# Controller.net
KiCad netlist of a schematic drawn in Altium Designer
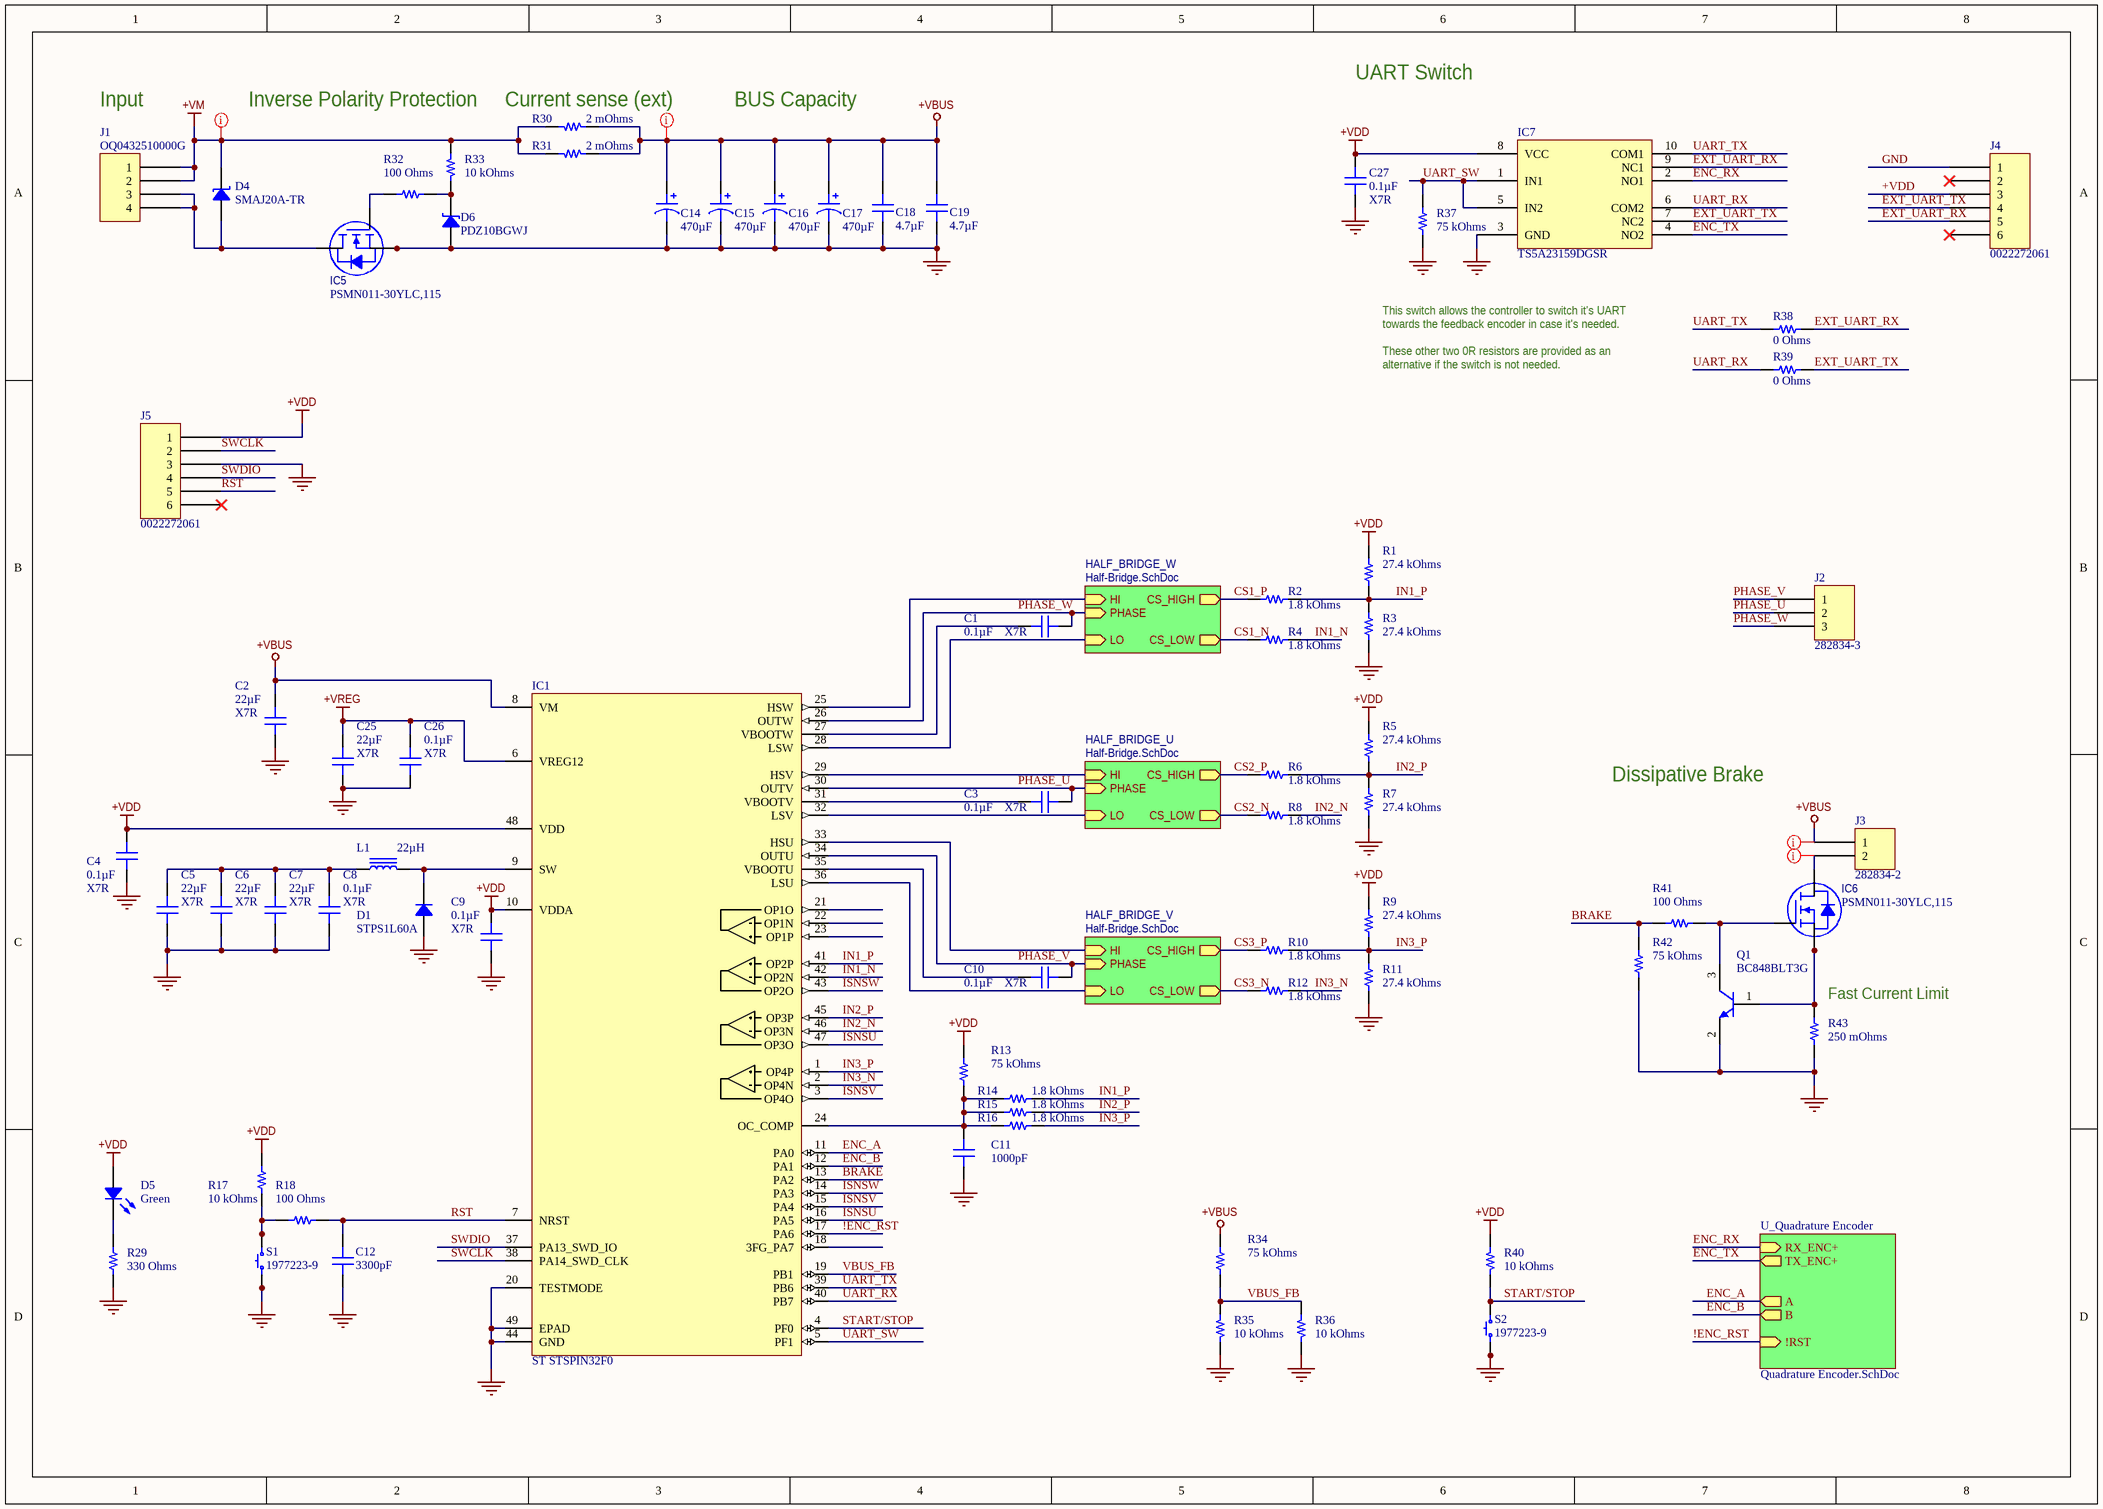
[diagram p0: Controller.SchDoc]

(export (version "E")
  (design (tool "Eeschema 10.0.6"))
  (components
    (comp (ref "C1")
      (value "0.1µF")
      (footprint "CAP 0805_2012")
      (description "CAP CER 0.1UF 50V X7R 0805")
      (fields
        (field (name "PART NUMBER") "CL21B104KBCWPNC")
        (field (name "MANUFACTURER") "Samsung Electro-Mechanics")
        (field (name "TEMPERATURE COEFFICIENT") "X7R")
      )
      (libsource (lib "Celestial Altium Library - altium_library") (part "Capacitor"))
    )
    (comp (ref "C2")
      (value "22µF")
      (footprint "CAP 1206_3216 - 1.8MM")
      (description "CAP CER 22UF 6.3V X7R 1206")
      (fields
        (field (name "PART NUMBER") "GCM31CR70J226KE23L")
        (field (name "MANUFACTURER") "Murata Electronics")
        (field (name "TEMPERATURE COEFFICIENT") "X7R")
      )
      (libsource (lib "Celestial Altium Library - altium_library") (part "Capacitor"))
    )
    (comp (ref "C3")
      (value "0.1µF")
      (footprint "CAP 0805_2012")
      (description "CAP CER 0.1UF 50V X7R 0805")
      (fields
        (field (name "PART NUMBER") "CL21B104KBCWPNC")
        (field (name "MANUFACTURER") "Samsung Electro-Mechanics")
        (field (name "TEMPERATURE COEFFICIENT") "X7R")
      )
      (libsource (lib "Celestial Altium Library - altium_library") (part "Capacitor"))
    )
    (comp (ref "C4")
      (value "0.1µF")
      (footprint "CAP 0805_2012")
      (description "CAP CER 0.1UF 50V X7R 0805")
      (fields
        (field (name "PART NUMBER") "CL21B104KBCWPNC")
        (field (name "MANUFACTURER") "Samsung Electro-Mechanics")
        (field (name "TEMPERATURE COEFFICIENT") "X7R")
      )
      (libsource (lib "Celestial Altium Library - altium_library") (part "Capacitor"))
    )
    (comp (ref "C5")
      (value "22µF")
      (footprint "CAP 1206_3216 - 1.8MM")
      (description "CAP CER 22UF 6.3V X7R 1206")
      (fields
        (field (name "PART NUMBER") "GCM31CR70J226KE23L")
        (field (name "MANUFACTURER") "Murata Electronics")
        (field (name "TEMPERATURE COEFFICIENT") "X7R")
      )
      (libsource (lib "Celestial Altium Library - altium_library") (part "Capacitor"))
    )
    (comp (ref "C6")
      (value "22µF")
      (footprint "CAP 1206_3216 - 1.8MM")
      (description "CAP CER 22UF 6.3V X7R 1206")
      (fields
        (field (name "PART NUMBER") "GCM31CR70J226KE23L")
        (field (name "MANUFACTURER") "Murata Electronics")
        (field (name "TEMPERATURE COEFFICIENT") "X7R")
      )
      (libsource (lib "Celestial Altium Library - altium_library") (part "Capacitor"))
    )
    (comp (ref "C7")
      (value "22µF")
      (footprint "CAP 1206_3216 - 1.8MM")
      (description "CAP CER 22UF 6.3V X7R 1206")
      (fields
        (field (name "PART NUMBER") "GCM31CR70J226KE23L")
        (field (name "MANUFACTURER") "Murata Electronics")
        (field (name "TEMPERATURE COEFFICIENT") "X7R")
      )
      (libsource (lib "Celestial Altium Library - altium_library") (part "Capacitor"))
    )
    (comp (ref "C8")
      (value "0.1µF")
      (footprint "CAP 0805_2012")
      (description "CAP CER 0.1UF 50V X7R 0805")
      (fields
        (field (name "PART NUMBER") "CL21B104KBCWPNC")
        (field (name "MANUFACTURER") "Samsung Electro-Mechanics")
        (field (name "TEMPERATURE COEFFICIENT") "X7R")
      )
      (libsource (lib "Celestial Altium Library - altium_library") (part "Capacitor"))
    )
    (comp (ref "C9")
      (value "0.1µF")
      (footprint "CAP 0805_2012")
      (description "CAP CER 0.1UF 50V X7R 0805")
      (fields
        (field (name "PART NUMBER") "CL21B104KBCWPNC")
        (field (name "MANUFACTURER") "Samsung Electro-Mechanics")
        (field (name "TEMPERATURE COEFFICIENT") "X7R")
      )
      (libsource (lib "Celestial Altium Library - altium_library") (part "Capacitor"))
    )
    (comp (ref "C10")
      (value "0.1µF")
      (footprint "CAP 0805_2012")
      (description "CAP CER 0.1UF 50V X7R 0805")
      (fields
        (field (name "PART NUMBER") "CL21B104KBCWPNC")
        (field (name "MANUFACTURER") "Samsung Electro-Mechanics")
        (field (name "TEMPERATURE COEFFICIENT") "X7R")
      )
      (libsource (lib "Celestial Altium Library - altium_library") (part "Capacitor"))
    )
    (comp (ref "C11")
      (value "1000pF")
      (footprint "CAP 0603_1608")
      (description "CAP CER 0603 1NF 16V X7R 10%")
      (fields (field (name "PART NUMBER") "C0603C102K4RECAUTO") (field (name "MANUFACTURER") "KEMET"))
      (libsource (lib "Celestial Altium Library - altium_library") (part "Capacitor"))
    )
    (comp (ref "C12")
      (value "3300pF")
      (footprint "CAP 0603_1608")
      (description "CAP CER 3300PF 25V NP0 0603")
      (fields (field (name "PART NUMBER") "C0603C332J3GAC7867") (field (name "MANUFACTURER") "KEMET"))
      (libsource (lib "Celestial Altium Library - altium_library") (part "Capacitor"))
    )
    (comp (ref "C14")
      (value "470µF")
      (footprint "CAP ALSMD 8.3MM H10.5MM")
      (description "CAP ALUM 470UF 20% 25V SMD")
      (fields (field (name "PART NUMBER") "25TPV470M8X10.5") (field (name "MANUFACTURER") "Rubycon"))
      (libsource (lib "Celestial Altium Library - altium_library") (part "Polarised Capacitor"))
    )
    (comp (ref "C15")
      (value "470µF")
      (footprint "CAP ALSMD 8.3MM H10.5MM")
      (description "CAP ALUM 470UF 20% 25V SMD")
      (fields (field (name "PART NUMBER") "25TPV470M8X10.5") (field (name "MANUFACTURER") "Rubycon"))
      (libsource (lib "Celestial Altium Library - altium_library") (part "Polarised Capacitor"))
    )
    (comp (ref "C16")
      (value "470µF")
      (footprint "CAP ALSMD 8.3MM H10.5MM")
      (description "CAP ALUM 470UF 20% 25V SMD")
      (fields (field (name "PART NUMBER") "25TPV470M8X10.5") (field (name "MANUFACTURER") "Rubycon"))
      (libsource (lib "Celestial Altium Library - altium_library") (part "Polarised Capacitor"))
    )
    (comp (ref "C17")
      (value "470µF")
      (footprint "CAP ALSMD 8.3MM H10.5MM")
      (description "CAP ALUM 470UF 20% 25V SMD")
      (fields (field (name "PART NUMBER") "25TPV470M8X10.5") (field (name "MANUFACTURER") "Rubycon"))
      (libsource (lib "Celestial Altium Library - altium_library") (part "Polarised Capacitor"))
    )
    (comp (ref "C18")
      (value "4.7µF")
      (footprint "CAP 1206_3216 - 1.8MM")
      (description "CAP CER 4.7UF 25V X7R 1206")
      (fields
        (field (name "PART NUMBER") "GCM31CR71E475KA55L")
        (field (name "MANUFACTURER") "Murata Electronics")
      )
      (libsource (lib "Celestial Altium Library - altium_library") (part "Capacitor"))
    )
    (comp (ref "C19")
      (value "4.7µF")
      (footprint "CAP 1206_3216 - 1.8MM")
      (description "CAP CER 4.7UF 25V X7R 1206")
      (fields
        (field (name "PART NUMBER") "GCM31CR71E475KA55L")
        (field (name "MANUFACTURER") "Murata Electronics")
      )
      (libsource (lib "Celestial Altium Library - altium_library") (part "Capacitor"))
    )
    (comp (ref "C25")
      (value "22µF")
      (footprint "CAP 1206_3216 - 1.8MM")
      (description "CAP CER 22UF 6.3V X7R 1206")
      (fields
        (field (name "PART NUMBER") "GCM31CR70J226KE23L")
        (field (name "MANUFACTURER") "Murata Electronics")
        (field (name "TEMPERATURE COEFFICIENT") "X7R")
      )
      (libsource (lib "Celestial Altium Library - altium_library") (part "Capacitor"))
    )
    (comp (ref "C26")
      (value "0.1µF")
      (footprint "CAP 0805_2012")
      (description "CAP CER 0.1UF 50V X7R 0805")
      (fields
        (field (name "PART NUMBER") "CL21B104KBCWPNC")
        (field (name "MANUFACTURER") "Samsung Electro-Mechanics")
        (field (name "TEMPERATURE COEFFICIENT") "X7R")
      )
      (libsource (lib "Celestial Altium Library - altium_library") (part "Capacitor"))
    )
    (comp (ref "C27")
      (value "0.1µF")
      (footprint "CAP 0805_2012")
      (description "CAP CER 0.1UF 50V X7R 0805")
      (fields
        (field (name "PART NUMBER") "CL21B104KBCWPNC")
        (field (name "MANUFACTURER") "Samsung Electro-Mechanics")
        (field (name "TEMPERATURE COEFFICIENT") "X7R")
      )
      (libsource (lib "Celestial Altium Library - altium_library") (part "Capacitor"))
    )
    (comp (ref "D1")
      (value "STPS1L60A")
      (footprint "DO214AC SMA")
      (description "DIODE SCHOTTKY 60V 1A SMA")
      (fields (field (name "MANUFACTURER") "STMicroelectronics"))
      (libsource (lib "Celestial Altium Library - altium_library") (part "Diode"))
    )
    (comp (ref "D4")
      (value "SMAJ20A-TR")
      (footprint "DO214AC SMA")
      (description "TVS DIODE 20V 42.8V SMA")
      (fields (field (name "MANUFACTURER") "STMicroelectronics"))
      (libsource (lib "Celestial Altium Library - altium_library") (part "DIODE TVS UNI"))
    )
    (comp (ref "D5")
      (value "Green")
      (footprint "LED 0603_1608 GREEN")
      (description "LED GREEN DIFFUSED 0603 SMD")
      (fields (field (name "PART NUMBER") "SML-D12P8WT86") (field (name "MANUFACTURER") "Rohm Semiconductor"))
      (libsource (lib "Celestial Altium Library - altium_library") (part "LED"))
    )
    (comp (ref "D6")
      (value "PDZ10BGWJ")
      (footprint "SOD-123")
      (description "DIODE ZENER 10V 365MW SOD123")
      (fields (field (name "MANUFACTURER") "Nexperia USA Inc.") (field (name "TOLERANCE") "±2.2%"))
      (libsource (lib "Celestial Altium Library - altium_library") (part "Diode Zener"))
    )
    (comp (ref "IC1")
      (value "ST STSPIN32F0")
      (footprint "PCB - LEADLESS - QFN - ST VFQFPN48 EP 5x5MM:ST VFQFPN48EP 7x7MM")
      (libsource (lib "SCH - MICROCONTROLLER - ST STSPIN32F0") (part "ST STSPIN32F0"))
    )
    (comp (ref "IC5")
      (value "PSMN011-30YLC,115")
      (footprint "NXP LFPAK56 SOT669")
      (description "MOSFET N-CH 30V 37A LFPAK")
      (fields (field (name "MANUFACTURER") "Nexperia USA Inc."))
      (libsource (lib "") (part "NEXPERIA PSMN LFPAK MOSFET N-CH_1"))
    )
    (comp (ref "IC6")
      (value "PSMN011-30YLC,115")
      (footprint "NXP LFPAK56 SOT669")
      (description "MOSFET N-CH 30V 37A LFPAK")
      (fields (field (name "MANUFACTURER") "Nexperia USA Inc."))
      (libsource (lib "Celestial Altium Library - altium_library") (part "NEXPERIA PSMN LFPAK MOSFET N-CH"))
    )
    (comp (ref "IC7")
      (value "TS5A23159DGSR")
      (footprint "TI MSOP-10 DGS")
      (description "IC SWITCH SPDT DUAL 10VSSOP")
      (fields (field (name "MANUFACTURER") "Texas Instruments"))
      (libsource (lib "Celestial Altium Library - altium_library") (part "TI TS5A23159"))
    )
    (comp (ref "J1")
      (value "OQ0432510000G")
      (footprint "FCI 06-381-4PIN")
      (description "TERM BLOCK HDR 4POS 90DEG 3.81MM")
      (fields (field (name "MANUFACTURER") "Amphenol Anytek"))
      (libsource (lib "Celestial Altium Library - altium_library") (part "4 Pin"))
    )
    (comp (ref "J2")
      (value "282834-3")
      (footprint "TE 282834-3")
      (description "TERM BLK 3P SIDE ENT 2.54MM PCB")
      (fields (field (name "MANUFACTURER") "TE Connectivity AMP Connectors") (field (name "VOLTAGE") "150V"))
      (libsource (lib "Celestial Altium Library - altium_library") (part "3 Pin"))
    )
    (comp (ref "J3")
      (value "282834-2")
      (footprint "TE 282834-2")
      (description "TERM BLK 2P SIDE ENT 2.54MM PCB")
      (fields (field (name "MANUFACTURER") "TE Connectivity AMP Connectors") (field (name "VOLTAGE") "150V"))
      (libsource (lib "Celestial Altium Library - altium_library") (part "2 Pin"))
    )
    (comp (ref "J4")
      (value "0022272061")
      (footprint "MOLEX KK 0022272061")
      (description "CONN HEADER VERT 6POS 2.54MM")
      (fields (field (name "MANUFACTURER") "Molex"))
      (libsource (lib "") (part "6 Pin_1"))
    )
    (comp (ref "J5")
      (value "0022272061")
      (footprint "MOLEX KK 0022272061")
      (description "CONN HEADER VERT 6POS 2.54MM")
      (fields (field (name "MANUFACTURER") "Molex"))
      (libsource (lib "Celestial Altium Library - altium_library") (part "6 Pin"))
    )
    (comp (ref "L1")
      (value "22µH")
      (footprint "BOURNS SRN3015")
      (description "FIXED IND 22UH 600MA 622MOHM SMD")
      (fields (field (name "PART NUMBER") "SRN3015-220M") (field (name "MANUFACTURER") "Bourns Inc."))
      (libsource (lib "Celestial Altium Library - altium_library") (part "Inductor"))
    )
    (comp (ref "Q1")
      (value "BC848BLT3G")
      (footprint "ON SEMI SOT-23-3")
      (description "TRANS NPN 30V 0.1A SOT-23")
      (fields (field (name "MANUFACTURER") "ON Semiconductor"))
      (libsource (lib "Celestial Altium Library - altium_library") (part "ON SEMI NPN SOT-23-3"))
    )
    (comp (ref "R1")
      (value "27.4 kOhms")
      (footprint "RES 0603_1608")
      (description "RES SMD 27.4K OHM 1% 1/10W 0603")
      (fields
        (field (name "PART NUMBER") "ERJ-3EKF2742V")
        (field (name "MANUFACTURER") "Panasonic Electronic Components")
      )
      (libsource (lib "Celestial Altium Library - altium_library") (part "Resistor"))
    )
    (comp (ref "R2")
      (value "1.8 kOhms")
      (footprint "RES 0603_1608")
      (description "RES SMD 1.8K OHM 1% 1/4W 0603")
      (fields
        (field (name "PART NUMBER") "ERJ-PA3F1801V")
        (field (name "MANUFACTURER") "Panasonic Electronic Components")
      )
      (libsource (lib "Celestial Altium Library - altium_library") (part "Resistor"))
    )
    (comp (ref "R3")
      (value "27.4 kOhms")
      (footprint "RES 0603_1608")
      (description "RES SMD 27.4K OHM 1% 1/10W 0603")
      (fields
        (field (name "PART NUMBER") "ERJ-3EKF2742V")
        (field (name "MANUFACTURER") "Panasonic Electronic Components")
      )
      (libsource (lib "Celestial Altium Library - altium_library") (part "Resistor"))
    )
    (comp (ref "R4")
      (value "1.8 kOhms")
      (footprint "RES 0603_1608")
      (description "RES SMD 1.8K OHM 1% 1/4W 0603")
      (fields
        (field (name "PART NUMBER") "ERJ-PA3F1801V")
        (field (name "MANUFACTURER") "Panasonic Electronic Components")
      )
      (libsource (lib "Celestial Altium Library - altium_library") (part "Resistor"))
    )
    (comp (ref "R5")
      (value "27.4 kOhms")
      (footprint "RES 0603_1608")
      (description "RES SMD 27.4K OHM 1% 1/10W 0603")
      (fields
        (field (name "PART NUMBER") "ERJ-3EKF2742V")
        (field (name "MANUFACTURER") "Panasonic Electronic Components")
      )
      (libsource (lib "Celestial Altium Library - altium_library") (part "Resistor"))
    )
    (comp (ref "R6")
      (value "1.8 kOhms")
      (footprint "RES 0603_1608")
      (description "RES SMD 1.8K OHM 1% 1/4W 0603")
      (fields
        (field (name "PART NUMBER") "ERJ-PA3F1801V")
        (field (name "MANUFACTURER") "Panasonic Electronic Components")
      )
      (libsource (lib "Celestial Altium Library - altium_library") (part "Resistor"))
    )
    (comp (ref "R7")
      (value "27.4 kOhms")
      (footprint "RES 0603_1608")
      (description "RES SMD 27.4K OHM 1% 1/10W 0603")
      (fields
        (field (name "PART NUMBER") "ERJ-3EKF2742V")
        (field (name "MANUFACTURER") "Panasonic Electronic Components")
      )
      (libsource (lib "Celestial Altium Library - altium_library") (part "Resistor"))
    )
    (comp (ref "R8")
      (value "1.8 kOhms")
      (footprint "RES 0603_1608")
      (description "RES SMD 1.8K OHM 1% 1/4W 0603")
      (fields
        (field (name "PART NUMBER") "ERJ-PA3F1801V")
        (field (name "MANUFACTURER") "Panasonic Electronic Components")
      )
      (libsource (lib "Celestial Altium Library - altium_library") (part "Resistor"))
    )
    (comp (ref "R9")
      (value "27.4 kOhms")
      (footprint "RES 0603_1608")
      (description "RES SMD 27.4K OHM 1% 1/10W 0603")
      (fields
        (field (name "PART NUMBER") "ERJ-3EKF2742V")
        (field (name "MANUFACTURER") "Panasonic Electronic Components")
      )
      (libsource (lib "Celestial Altium Library - altium_library") (part "Resistor"))
    )
    (comp (ref "R10")
      (value "1.8 kOhms")
      (footprint "RES 0603_1608")
      (description "RES SMD 1.8K OHM 1% 1/4W 0603")
      (fields
        (field (name "PART NUMBER") "ERJ-PA3F1801V")
        (field (name "MANUFACTURER") "Panasonic Electronic Components")
      )
      (libsource (lib "Celestial Altium Library - altium_library") (part "Resistor"))
    )
    (comp (ref "R11")
      (value "27.4 kOhms")
      (footprint "RES 0603_1608")
      (description "RES SMD 27.4K OHM 1% 1/10W 0603")
      (fields
        (field (name "PART NUMBER") "ERJ-3EKF2742V")
        (field (name "MANUFACTURER") "Panasonic Electronic Components")
      )
      (libsource (lib "Celestial Altium Library - altium_library") (part "Resistor"))
    )
    (comp (ref "R12")
      (value "1.8 kOhms")
      (footprint "RES 0603_1608")
      (description "RES SMD 1.8K OHM 1% 1/4W 0603")
      (fields
        (field (name "PART NUMBER") "ERJ-PA3F1801V")
        (field (name "MANUFACTURER") "Panasonic Electronic Components")
      )
      (libsource (lib "Celestial Altium Library - altium_library") (part "Resistor"))
    )
    (comp (ref "R13")
      (value "75 kOhms")
      (footprint "RES 0603_1608")
      (description "RES SMD 75K OHM 1% 1/10W 0603")
      (fields
        (field (name "PART NUMBER") "ERJ-3EKF7502V")
        (field (name "MANUFACTURER") "Panasonic Electronic Components")
      )
      (libsource (lib "Celestial Altium Library - altium_library") (part "Resistor"))
    )
    (comp (ref "R14")
      (value "1.8 kOhms")
      (footprint "RES 0603_1608")
      (description "RES SMD 1.8K OHM 1% 1/4W 0603")
      (fields
        (field (name "PART NUMBER") "ERJ-PA3F1801V")
        (field (name "MANUFACTURER") "Panasonic Electronic Components")
      )
      (libsource (lib "Celestial Altium Library - altium_library") (part "Resistor"))
    )
    (comp (ref "R15")
      (value "1.8 kOhms")
      (footprint "RES 0603_1608")
      (description "RES SMD 1.8K OHM 1% 1/4W 0603")
      (fields
        (field (name "PART NUMBER") "ERJ-PA3F1801V")
        (field (name "MANUFACTURER") "Panasonic Electronic Components")
      )
      (libsource (lib "Celestial Altium Library - altium_library") (part "Resistor"))
    )
    (comp (ref "R16")
      (value "1.8 kOhms")
      (footprint "RES 0603_1608")
      (description "RES SMD 1.8K OHM 1% 1/4W 0603")
      (fields
        (field (name "PART NUMBER") "ERJ-PA3F1801V")
        (field (name "MANUFACTURER") "Panasonic Electronic Components")
      )
      (libsource (lib "Celestial Altium Library - altium_library") (part "Resistor"))
    )
    (comp (ref "R17")
      (value "10 kOhms")
      (footprint "RES 0603_1608")
      (description "RES SMD 10K OHM 1% 1/4W 0603")
      (fields (field (name "PART NUMBER") "ESR03EZPF1002") (field (name "MANUFACTURER") "Rohm Semiconductor"))
      (libsource (lib "Celestial Altium Library - altium_library") (part "Resistor"))
    )
    (comp (ref "R18")
      (value "100 Ohms")
      (footprint "RES 0603_1608")
      (description "RES 100 OHM 1% 1/8W 0603")
      (fields
        (field (name "PART NUMBER") "RNCP0603FTD100R")
        (field (name "MANUFACTURER") "Stackpole Electronics Inc")
      )
      (libsource (lib "Celestial Altium Library - altium_library") (part "Resistor"))
    )
    (comp (ref "R29")
      (value "330 Ohms")
      (footprint "RES 0603_1608")
      (description "RES SMD 330 OHM 1% 1/5W 0603")
      (fields
        (field (name "PART NUMBER") "CRGH0603F330R")
        (field (name "MANUFACTURER") "TE Connectivity Passive Product")
      )
      (libsource (lib "Celestial Altium Library - altium_library") (part "Resistor"))
    )
    (comp (ref "R30")
      (value "2 mOhms")
      (footprint "RES 1210_3225")
      (description "RES 0.002 OHM 1% 1W 1210")
      (fields
        (field (name "PART NUMBER") "PMR25HZPFV2L00")
        (field (name "MANUFACTURER") "Rohm Semiconductor")
      )
      (libsource (lib "Celestial Altium Library - altium_library") (part "Resistor"))
    )
    (comp (ref "R31")
      (value "2 mOhms")
      (footprint "RES 1210_3225")
      (description "RES 0.002 OHM 1% 1W 1210")
      (fields
        (field (name "PART NUMBER") "PMR25HZPFV2L00")
        (field (name "MANUFACTURER") "Rohm Semiconductor")
      )
      (libsource (lib "Celestial Altium Library - altium_library") (part "Resistor"))
    )
    (comp (ref "R32")
      (value "100 Ohms")
      (footprint "RES 0603_1608")
      (description "RES 100 OHM 1% 1/8W 0603")
      (fields
        (field (name "PART NUMBER") "RNCP0603FTD100R")
        (field (name "MANUFACTURER") "Stackpole Electronics Inc")
      )
      (libsource (lib "Celestial Altium Library - altium_library") (part "Resistor"))
    )
    (comp (ref "R33")
      (value "10 kOhms")
      (footprint "RES 0603_1608")
      (description "RES SMD 10K OHM 1% 1/4W 0603")
      (fields (field (name "PART NUMBER") "ESR03EZPF1002") (field (name "MANUFACTURER") "Rohm Semiconductor"))
      (libsource (lib "Celestial Altium Library - altium_library") (part "Resistor"))
    )
    (comp (ref "R34")
      (value "75 kOhms")
      (footprint "RES 0603_1608")
      (description "RES SMD 75K OHM 1% 1/10W 0603")
      (fields
        (field (name "PART NUMBER") "ERJ-3EKF7502V")
        (field (name "MANUFACTURER") "Panasonic Electronic Components")
      )
      (libsource (lib "Celestial Altium Library - altium_library") (part "Resistor"))
    )
    (comp (ref "R35")
      (value "10 kOhms")
      (footprint "RES 0603_1608")
      (description "RES SMD 10K OHM 1% 1/4W 0603")
      (fields (field (name "PART NUMBER") "ESR03EZPF1002") (field (name "MANUFACTURER") "Rohm Semiconductor"))
      (libsource (lib "Celestial Altium Library - altium_library") (part "Resistor"))
    )
    (comp (ref "R36")
      (value "10 kOhms")
      (footprint "RES 0603_1608")
      (description "RES SMD 10K OHM 1% 1/4W 0603")
      (fields (field (name "PART NUMBER") "ESR03EZPF1002") (field (name "MANUFACTURER") "Rohm Semiconductor"))
      (libsource (lib "Celestial Altium Library - altium_library") (part "Resistor"))
    )
    (comp (ref "R37")
      (value "75 kOhms")
      (footprint "RES 0603_1608")
      (description "RES SMD 75K OHM 1% 1/10W 0603")
      (fields
        (field (name "PART NUMBER") "ERJ-3EKF7502V")
        (field (name "MANUFACTURER") "Panasonic Electronic Components")
      )
      (libsource (lib "Celestial Altium Library - altium_library") (part "Resistor"))
    )
    (comp (ref "R38")
      (value "0 Ohms")
      (footprint "RES 0603_1608")
      (description "RES SMD 0 OHM JUMPER 1/4W 0603")
      (fields (field (name "PART NUMBER") "CRCW06030000Z0EAHP") (field (name "MANUFACTURER") "Vishay Dale"))
      (libsource (lib "Celestial Altium Library - altium_library") (part "Resistor"))
    )
    (comp (ref "R39")
      (value "0 Ohms")
      (footprint "RES 0603_1608")
      (description "RES SMD 0 OHM JUMPER 1/4W 0603")
      (fields (field (name "PART NUMBER") "CRCW06030000Z0EAHP") (field (name "MANUFACTURER") "Vishay Dale"))
      (libsource (lib "Celestial Altium Library - altium_library") (part "Resistor"))
    )
    (comp (ref "R40")
      (value "10 kOhms")
      (footprint "RES 0603_1608")
      (description "RES SMD 10K OHM 1% 1/4W 0603")
      (fields (field (name "PART NUMBER") "ESR03EZPF1002") (field (name "MANUFACTURER") "Rohm Semiconductor"))
      (libsource (lib "Celestial Altium Library - altium_library") (part "Resistor"))
    )
    (comp (ref "R41")
      (value "100 Ohms")
      (footprint "RES 0603_1608")
      (description "RES 100 OHM 1% 1/8W 0603")
      (fields
        (field (name "PART NUMBER") "RNCP0603FTD100R")
        (field (name "MANUFACTURER") "Stackpole Electronics Inc")
      )
      (libsource (lib "Celestial Altium Library - altium_library") (part "Resistor"))
    )
    (comp (ref "R42")
      (value "75 kOhms")
      (footprint "RES 0603_1608")
      (description "RES SMD 75K OHM 1% 1/10W 0603")
      (fields
        (field (name "PART NUMBER") "ERJ-3EKF7502V")
        (field (name "MANUFACTURER") "Panasonic Electronic Components")
      )
      (libsource (lib "Celestial Altium Library - altium_library") (part "Resistor"))
    )
    (comp (ref "R43")
      (value "250 mOhms")
      (footprint "RES 2512_6432")
      (description "RES 0.25 OHM 1% 2W 2512")
      (fields (field (name "PART NUMBER") "CRM2512-FX-R250ELF") (field (name "MANUFACTURER") "Bourns Inc."))
      (libsource (lib "Celestial Altium Library - altium_library") (part "Resistor"))
    )
    (comp (ref "S1")
      (value "1977223-9")
      (footprint "TE FSM4JSMA")
      (description "SWITCH TACTILE SPST-NO 0.05A 24V")
      (fields (field (name "MANUFACTURER") "TE Connectivity ALCOSWITCH Switches"))
      (libsource (lib "Celestial Altium Library - altium_library") (part "SPST-NO 4 PIN"))
    )
    (comp (ref "S2")
      (value "1977223-9")
      (footprint "TE FSM4JSMA")
      (description "SWITCH TACTILE SPST-NO 0.05A 24V")
      (fields (field (name "MANUFACTURER") "TE Connectivity ALCOSWITCH Switches"))
      (libsource (lib "Celestial Altium Library - altium_library") (part "SPST-NO 4 PIN"))
    )
  )
  (nets
    (net (code "1") (name "+VBUS") (class "Default")
      (node (ref "C14") (pin "1") (pinfunction "1_1") (pintype "passive"))
      (node (ref "C15") (pin "1") (pinfunction "1_1") (pintype "passive"))
      (node (ref "C16") (pin "1") (pinfunction "1_1") (pintype "passive"))
      (node (ref "C17") (pin "1") (pinfunction "1_1") (pintype "passive"))
      (node (ref "C18") (pin "2") (pinfunction "2_2") (pintype "passive"))
      (node (ref "C19") (pin "2") (pinfunction "2_2") (pintype "passive"))
      (node (ref "C2") (pin "2") (pinfunction "2_2") (pintype "passive"))
      (node (ref "IC1") (pin "8") (pinfunction "VM_8") (pintype "power_in"))
      (node (ref "J3") (pin "1") (pinfunction "1_1") (pintype "passive"))
      (node (ref "R30") (pin "1") (pinfunction "1_1") (pintype "passive"))
      (node (ref "R31") (pin "1") (pinfunction "1_1") (pintype "passive"))
      (node (ref "R34") (pin "2") (pinfunction "2_2") (pintype "passive"))
    )
    (net (code "2") (name "+VDD") (class "Default")
      (node (ref "C27") (pin "1") (pinfunction "1_1") (pintype "passive"))
      (node (ref "C4") (pin "1") (pinfunction "1_1") (pintype "passive"))
      (node (ref "C9") (pin "1") (pinfunction "1_1") (pintype "passive"))
      (node (ref "D5") (pin "1") (pinfunction "1_1") (pintype "passive"))
      (node (ref "IC1") (pin "10") (pinfunction "VDDA_10") (pintype "power_in"))
      (node (ref "IC1") (pin "48") (pinfunction "VDD_48") (pintype "power_in"))
      (node (ref "IC7") (pin "8") (pinfunction "VCC_8") (pintype "passive"))
      (node (ref "J4") (pin "3") (pinfunction "3_3") (pintype "passive"))
      (node (ref "J5") (pin "1") (pinfunction "1_1") (pintype "passive"))
      (node (ref "R1") (pin "2") (pinfunction "2_2") (pintype "passive"))
      (node (ref "R13") (pin "2") (pinfunction "2_2") (pintype "passive"))
      (node (ref "R17") (pin "2") (pinfunction "2_2") (pintype "passive"))
      (node (ref "R40") (pin "2") (pinfunction "2_2") (pintype "passive"))
      (node (ref "R5") (pin "2") (pinfunction "2_2") (pintype "passive"))
      (node (ref "R9") (pin "2") (pinfunction "2_2") (pintype "passive"))
    )
    (net (code "3") (name "+VM") (class "Default")
      (node (ref "D4") (pin "2") (pinfunction "2_2") (pintype "passive"))
      (node (ref "J1") (pin "1") (pinfunction "1_1") (pintype "passive"))
      (node (ref "J1") (pin "2") (pinfunction "2_2") (pintype "passive"))
      (node (ref "R30") (pin "2") (pinfunction "2_2") (pintype "passive"))
      (node (ref "R31") (pin "2") (pinfunction "2_2") (pintype "passive"))
      (node (ref "R33") (pin "2") (pinfunction "2_2") (pintype "passive"))
    )
    (net (code "4") (name "+VREG") (class "Default")
      (node (ref "C25") (pin "2") (pinfunction "2_2") (pintype "passive"))
      (node (ref "C26") (pin "1") (pinfunction "1_1") (pintype "passive"))
      (node (ref "IC1") (pin "6") (pinfunction "VREG12_6") (pintype "power_in"))
    )
    (net (code "5") (name "/!ENC_RST") (class "Default")
      (node (ref "IC1") (pin "17") (pinfunction "PA6_17") (pintype "bidirectional"))
    )
    (net (code "6") (name "/BRAKE") (class "Default")
      (node (ref "IC1") (pin "13") (pinfunction "PA2_13") (pintype "bidirectional"))
      (node (ref "R41") (pin "1") (pinfunction "1_1") (pintype "passive"))
      (node (ref "R42") (pin "2") (pinfunction "2_2") (pintype "passive"))
    )
    (net (code "7") (name "/CS1_N") (class "Default")
      (node (ref "R4") (pin "1") (pinfunction "1_1") (pintype "passive"))
    )
    (net (code "8") (name "/CS1_P") (class "Default")
      (node (ref "R2") (pin "1") (pinfunction "1_1") (pintype "passive"))
    )
    (net (code "9") (name "/CS2_N") (class "Default")
      (node (ref "R8") (pin "1") (pinfunction "1_1") (pintype "passive"))
    )
    (net (code "10") (name "/CS2_P") (class "Default")
      (node (ref "R6") (pin "1") (pinfunction "1_1") (pintype "passive"))
    )
    (net (code "11") (name "/CS3_N") (class "Default")
      (node (ref "R12") (pin "1") (pinfunction "1_1") (pintype "passive"))
    )
    (net (code "12") (name "/CS3_P") (class "Default")
      (node (ref "R10") (pin "1") (pinfunction "1_1") (pintype "passive"))
    )
    (net (code "13") (name "/ENC_A") (class "Default")
      (node (ref "IC1") (pin "11") (pinfunction "PA0_11") (pintype "bidirectional"))
    )
    (net (code "14") (name "/ENC_B") (class "Default")
      (node (ref "IC1") (pin "12") (pinfunction "PA1_12") (pintype "bidirectional"))
    )
    (net (code "15") (name "/ENC_RX") (class "Default")
      (node (ref "IC7") (pin "2") (pinfunction "NO1_2") (pintype "passive"))
    )
    (net (code "16") (name "/ENC_TX") (class "Default")
      (node (ref "IC7") (pin "4") (pinfunction "NO2_4") (pintype "passive"))
    )
    (net (code "17") (name "/EXT_UART_RX") (class "Default")
      (node (ref "IC7") (pin "9") (pinfunction "NC1_9") (pintype "passive"))
      (node (ref "J4") (pin "5") (pinfunction "5_5") (pintype "passive"))
      (node (ref "R38") (pin "2") (pinfunction "2_2") (pintype "passive"))
    )
    (net (code "18") (name "/EXT_UART_TX") (class "Default")
      (node (ref "IC7") (pin "7") (pinfunction "NC2_7") (pintype "passive"))
      (node (ref "J4") (pin "4") (pinfunction "4_4") (pintype "passive"))
      (node (ref "R39") (pin "2") (pinfunction "2_2") (pintype "passive"))
    )
    (net (code "19") (name "/HI") (class "Default")
      (node (ref "IC1") (pin "33") (pinfunction "HSU_33") (pintype "output"))
    )
    (net (code "20") (name "/HI_1") (class "Default")
      (node (ref "IC1") (pin "25") (pinfunction "HSW_25") (pintype "output"))
    )
    (net (code "21") (name "/HI_2") (class "Default")
      (node (ref "IC1") (pin "29") (pinfunction "HSV_29") (pintype "output"))
    )
    (net (code "22") (name "/IN1_N") (class "Default")
      (node (ref "IC1") (pin "42") (pinfunction "OP2N_42") (pintype "input"))
      (node (ref "R4") (pin "2") (pinfunction "2_2") (pintype "passive"))
    )
    (net (code "23") (name "/IN1_P") (class "Default")
      (node (ref "IC1") (pin "41") (pinfunction "OP2P_41") (pintype "input"))
      (node (ref "R1") (pin "1") (pinfunction "1_1") (pintype "passive"))
      (node (ref "R14") (pin "2") (pinfunction "2_2") (pintype "passive"))
      (node (ref "R2") (pin "2") (pinfunction "2_2") (pintype "passive"))
      (node (ref "R3") (pin "2") (pinfunction "2_2") (pintype "passive"))
    )
    (net (code "24") (name "/IN2_N") (class "Default")
      (node (ref "IC1") (pin "46") (pinfunction "OP3N_46") (pintype "input"))
      (node (ref "R8") (pin "2") (pinfunction "2_2") (pintype "passive"))
    )
    (net (code "25") (name "/IN2_P") (class "Default")
      (node (ref "IC1") (pin "45") (pinfunction "OP3P_45") (pintype "input"))
      (node (ref "R15") (pin "2") (pinfunction "2_2") (pintype "passive"))
      (node (ref "R5") (pin "1") (pinfunction "1_1") (pintype "passive"))
      (node (ref "R6") (pin "2") (pinfunction "2_2") (pintype "passive"))
      (node (ref "R7") (pin "2") (pinfunction "2_2") (pintype "passive"))
    )
    (net (code "26") (name "/IN3_N") (class "Default")
      (node (ref "IC1") (pin "2") (pinfunction "OP4N_2") (pintype "input"))
      (node (ref "R12") (pin "2") (pinfunction "2_2") (pintype "passive"))
    )
    (net (code "27") (name "/IN3_P") (class "Default")
      (node (ref "IC1") (pin "1") (pinfunction "OP4P_1") (pintype "input"))
      (node (ref "R10") (pin "2") (pinfunction "2_2") (pintype "passive"))
      (node (ref "R11") (pin "2") (pinfunction "2_2") (pintype "passive"))
      (node (ref "R16") (pin "2") (pinfunction "2_2") (pintype "passive"))
      (node (ref "R9") (pin "1") (pinfunction "1_1") (pintype "passive"))
    )
    (net (code "28") (name "/ISNSU") (class "Default")
      (node (ref "IC1") (pin "16") (pinfunction "PA5_16") (pintype "bidirectional"))
      (node (ref "IC1") (pin "47") (pinfunction "OP3O_47") (pintype "output"))
    )
    (net (code "29") (name "/ISNSV") (class "Default")
      (node (ref "IC1") (pin "15") (pinfunction "PA4_15") (pintype "bidirectional"))
      (node (ref "IC1") (pin "3") (pinfunction "OP4O_3") (pintype "output"))
    )
    (net (code "30") (name "/ISNSW") (class "Default")
      (node (ref "IC1") (pin "14") (pinfunction "PA3_14") (pintype "bidirectional"))
      (node (ref "IC1") (pin "43") (pinfunction "OP2O_43") (pintype "output"))
    )
    (net (code "31") (name "/LO") (class "Default")
      (node (ref "IC1") (pin "36") (pinfunction "LSU_36") (pintype "output"))
    )
    (net (code "32") (name "/LO_1") (class "Default")
      (node (ref "IC1") (pin "28") (pinfunction "LSW_28") (pintype "output"))
    )
    (net (code "33") (name "/LO_2") (class "Default")
      (node (ref "IC1") (pin "32") (pinfunction "LSV_32") (pintype "output"))
    )
    (net (code "34") (name "/PHASE_U") (class "Default")
      (node (ref "C3") (pin "1") (pinfunction "1_1") (pintype "passive"))
      (node (ref "IC1") (pin "30") (pinfunction "OUTV_30") (pintype "input"))
      (node (ref "J2") (pin "2") (pinfunction "2_2") (pintype "passive"))
    )
    (net (code "35") (name "/PHASE_V") (class "Default")
      (node (ref "C10") (pin "1") (pinfunction "1_1") (pintype "passive"))
      (node (ref "IC1") (pin "34") (pinfunction "OUTU_34") (pintype "input"))
      (node (ref "J2") (pin "1") (pinfunction "1_1") (pintype "passive"))
    )
    (net (code "36") (name "/PHASE_W") (class "Default")
      (node (ref "C1") (pin "1") (pinfunction "1_1") (pintype "passive"))
      (node (ref "IC1") (pin "26") (pinfunction "OUTW_26") (pintype "input"))
      (node (ref "J2") (pin "3") (pinfunction "3_3") (pintype "passive"))
    )
    (net (code "37") (name "/RST") (class "Default")
      (node (ref "C12") (pin "2") (pinfunction "2_2") (pintype "passive"))
      (node (ref "IC1") (pin "7") (pinfunction "NRST_7") (pintype "passive"))
      (node (ref "J5") (pin "5") (pinfunction "5_5") (pintype "passive"))
      (node (ref "R18") (pin "2") (pinfunction "2_2") (pintype "passive"))
    )
    (net (code "38") (name "/START{slash}STOP") (class "Default")
      (node (ref "IC1") (pin "4") (pinfunction "PF0_4") (pintype "bidirectional"))
      (node (ref "R40") (pin "1") (pinfunction "1_1") (pintype "passive"))
      (node (ref "S2") (pin "3") (pinfunction "3_3") (pintype "passive"))
      (node (ref "S2") (pin "4") (pinfunction "4_4") (pintype "passive"))
    )
    (net (code "39") (name "/SWCLK") (class "Default")
      (node (ref "IC1") (pin "38") (pinfunction "PA14_SWD_CLK_38") (pintype "passive"))
      (node (ref "J5") (pin "2") (pinfunction "2_2") (pintype "passive"))
    )
    (net (code "40") (name "/SWDIO") (class "Default")
      (node (ref "IC1") (pin "37") (pinfunction "PA13_SWD_IO_37") (pintype "passive"))
      (node (ref "J5") (pin "4") (pinfunction "4_4") (pintype "passive"))
    )
    (net (code "41") (name "/UART_RX") (class "Default")
      (node (ref "IC1") (pin "40") (pinfunction "PB7_40") (pintype "bidirectional"))
      (node (ref "IC7") (pin "6") (pinfunction "COM2_6") (pintype "passive"))
      (node (ref "R39") (pin "1") (pinfunction "1_1") (pintype "passive"))
    )
    (net (code "42") (name "/UART_SW") (class "Default")
      (node (ref "IC1") (pin "5") (pinfunction "PF1_5") (pintype "bidirectional"))
      (node (ref "IC7") (pin "1") (pinfunction "IN1_1") (pintype "passive"))
      (node (ref "IC7") (pin "5") (pinfunction "IN2_5") (pintype "passive"))
      (node (ref "R37") (pin "2") (pinfunction "2_2") (pintype "passive"))
    )
    (net (code "43") (name "/UART_TX") (class "Default")
      (node (ref "IC1") (pin "39") (pinfunction "PB6_39") (pintype "bidirectional"))
      (node (ref "IC7") (pin "10") (pinfunction "COM1_10") (pintype "passive"))
      (node (ref "R38") (pin "1") (pinfunction "1_1") (pintype "passive"))
    )
    (net (code "44") (name "/VBUS_FB") (class "Default")
      (node (ref "IC1") (pin "19") (pinfunction "PB1_19") (pintype "bidirectional"))
      (node (ref "R34") (pin "1") (pinfunction "1_1") (pintype "passive"))
      (node (ref "R35") (pin "2") (pinfunction "2_2") (pintype "passive"))
      (node (ref "R36") (pin "2") (pinfunction "2_2") (pintype "passive"))
    )
    (net (code "45") (name "GND") (class "Default")
      (node (ref "C11") (pin "1") (pinfunction "1_1") (pintype "passive"))
      (node (ref "C12") (pin "1") (pinfunction "1_1") (pintype "passive"))
      (node (ref "C14") (pin "2") (pinfunction "2_2") (pintype "passive"))
      (node (ref "C15") (pin "2") (pinfunction "2_2") (pintype "passive"))
      (node (ref "C16") (pin "2") (pinfunction "2_2") (pintype "passive"))
      (node (ref "C17") (pin "2") (pinfunction "2_2") (pintype "passive"))
      (node (ref "C18") (pin "1") (pinfunction "1_1") (pintype "passive"))
      (node (ref "C19") (pin "1") (pinfunction "1_1") (pintype "passive"))
      (node (ref "C2") (pin "1") (pinfunction "1_1") (pintype "passive"))
      (node (ref "C25") (pin "1") (pinfunction "1_1") (pintype "passive"))
      (node (ref "C26") (pin "2") (pinfunction "2_2") (pintype "passive"))
      (node (ref "C27") (pin "2") (pinfunction "2_2") (pintype "passive"))
      (node (ref "C4") (pin "2") (pinfunction "2_2") (pintype "passive"))
      (node (ref "C5") (pin "1") (pinfunction "1_1") (pintype "passive"))
      (node (ref "C6") (pin "1") (pinfunction "1_1") (pintype "passive"))
      (node (ref "C7") (pin "1") (pinfunction "1_1") (pintype "passive"))
      (node (ref "C8") (pin "2") (pinfunction "2_2") (pintype "passive"))
      (node (ref "C9") (pin "2") (pinfunction "2_2") (pintype "passive"))
      (node (ref "D1") (pin "1") (pinfunction "1_1") (pintype "passive"))
      (node (ref "D6") (pin "1") (pinfunction "1_1") (pintype "passive"))
      (node (ref "IC1") (pin "20") (pinfunction "TESTMODE_20") (pintype "passive"))
      (node (ref "IC1") (pin "44") (pinfunction "GND_44") (pintype "power_in"))
      (node (ref "IC1") (pin "49") (pinfunction "EPAD_49") (pintype "power_in"))
      (node (ref "IC5") (pin "1") (pinfunction "S_1") (pintype "passive"))
      (node (ref "IC5") (pin "2") (pinfunction "S_2") (pintype "passive"))
      (node (ref "IC5") (pin "3") (pinfunction "S_3") (pintype "passive"))
      (node (ref "IC7") (pin "3") (pinfunction "GND_3") (pintype "passive"))
      (node (ref "J4") (pin "1") (pinfunction "1_1") (pintype "passive"))
      (node (ref "J5") (pin "3") (pinfunction "3_3") (pintype "passive"))
      (node (ref "Q1") (pin "2") (pinfunction "E_2") (pintype "passive"))
      (node (ref "R11") (pin "1") (pinfunction "1_1") (pintype "passive"))
      (node (ref "R29") (pin "1") (pinfunction "1_1") (pintype "passive"))
      (node (ref "R3") (pin "1") (pinfunction "1_1") (pintype "passive"))
      (node (ref "R35") (pin "1") (pinfunction "1_1") (pintype "passive"))
      (node (ref "R36") (pin "1") (pinfunction "1_1") (pintype "passive"))
      (node (ref "R37") (pin "1") (pinfunction "1_1") (pintype "passive"))
      (node (ref "R42") (pin "1") (pinfunction "1_1") (pintype "passive"))
      (node (ref "R43") (pin "1") (pinfunction "1_1") (pintype "passive"))
      (node (ref "R7") (pin "1") (pinfunction "1_1") (pintype "passive"))
      (node (ref "S1") (pin "1") (pinfunction "1_1") (pintype "passive"))
      (node (ref "S1") (pin "2") (pinfunction "2_2") (pintype "passive"))
      (node (ref "S2") (pin "1") (pinfunction "1_1") (pintype "passive"))
      (node (ref "S2") (pin "2") (pinfunction "2_2") (pintype "passive"))
    )
    (net (code "46") (name "Net-(C5-Pad2)") (class "Default")
      (node (ref "C5") (pin "2") (pinfunction "2_2") (pintype "passive"))
      (node (ref "C6") (pin "2") (pinfunction "2_2") (pintype "passive"))
      (node (ref "C7") (pin "2") (pinfunction "2_2") (pintype "passive"))
      (node (ref "C8") (pin "1") (pinfunction "1_1") (pintype "passive"))
      (node (ref "L1") (pin "1") (pinfunction "1_1") (pintype "passive"))
    )
    (net (code "47") (name "Net-(D5-Pad2)") (class "Default")
      (node (ref "D5") (pin "2") (pinfunction "2_2") (pintype "passive"))
      (node (ref "R29") (pin "2") (pinfunction "2_2") (pintype "passive"))
    )
    (net (code "48") (name "Net-(D6-Pad2)") (class "Default")
      (node (ref "D6") (pin "2") (pinfunction "2_2") (pintype "passive"))
      (node (ref "R32") (pin "2") (pinfunction "2_2") (pintype "passive"))
      (node (ref "R33") (pin "1") (pinfunction "1_1") (pintype "passive"))
    )
    (net (code "49") (name "Net-(IC1-OC_COMP)") (class "Default")
      (node (ref "C11") (pin "2") (pinfunction "2_2") (pintype "passive"))
      (node (ref "IC1") (pin "24") (pinfunction "OC_COMP_24") (pintype "passive"))
      (node (ref "R13") (pin "1") (pinfunction "1_1") (pintype "passive"))
      (node (ref "R14") (pin "1") (pinfunction "1_1") (pintype "passive"))
      (node (ref "R15") (pin "1") (pinfunction "1_1") (pintype "passive"))
      (node (ref "R16") (pin "1") (pinfunction "1_1") (pintype "passive"))
    )
    (net (code "50") (name "Net-(IC1-SW)") (class "Default")
      (node (ref "D1") (pin "2") (pinfunction "2_2") (pintype "passive"))
      (node (ref "IC1") (pin "9") (pinfunction "SW_9") (pintype "power_in"))
      (node (ref "L1") (pin "2") (pinfunction "2_2") (pintype "passive"))
    )
    (net (code "51") (name "Net-(IC1-VBOOTU)") (class "Default")
      (node (ref "C10") (pin "2") (pinfunction "2_2") (pintype "passive"))
      (node (ref "IC1") (pin "35") (pinfunction "VBOOTU_35") (pintype "passive"))
    )
    (net (code "52") (name "Net-(IC1-VBOOTV)") (class "Default")
      (node (ref "C3") (pin "2") (pinfunction "2_2") (pintype "passive"))
      (node (ref "IC1") (pin "31") (pinfunction "VBOOTV_31") (pintype "passive"))
    )
    (net (code "53") (name "Net-(IC1-VBOOTW)") (class "Default")
      (node (ref "C1") (pin "2") (pinfunction "2_2") (pintype "passive"))
      (node (ref "IC1") (pin "27") (pinfunction "VBOOTW_27") (pintype "passive"))
    )
    (net (code "54") (name "Net-(IC5-D)") (class "Default")
      (node (ref "D4") (pin "1") (pinfunction "1_1") (pintype "passive"))
      (node (ref "IC5") (pin "5") (pinfunction "D_5") (pintype "passive"))
      (node (ref "J1") (pin "3") (pinfunction "3_3") (pintype "passive"))
      (node (ref "J1") (pin "4") (pinfunction "4_4") (pintype "passive"))
    )
    (net (code "55") (name "Net-(IC5-G)") (class "Default")
      (node (ref "IC5") (pin "4") (pinfunction "G_4") (pintype "passive"))
      (node (ref "R32") (pin "1") (pinfunction "1_1") (pintype "passive"))
    )
    (net (code "56") (name "Net-(IC6-D)") (class "Default")
      (node (ref "IC6") (pin "5") (pinfunction "D_5") (pintype "passive"))
      (node (ref "J3") (pin "2") (pinfunction "2_2") (pintype "passive"))
    )
    (net (code "57") (name "Net-(IC6-G)") (class "Default")
      (node (ref "IC6") (pin "4") (pinfunction "G_4") (pintype "passive"))
      (node (ref "Q1") (pin "3") (pinfunction "C_3") (pintype "passive"))
      (node (ref "R41") (pin "2") (pinfunction "2_2") (pintype "passive"))
    )
    (net (code "58") (name "Net-(Q1-B)") (class "Default")
      (node (ref "IC6") (pin "1") (pinfunction "S_1") (pintype "passive"))
      (node (ref "IC6") (pin "2") (pinfunction "S_2") (pintype "passive"))
      (node (ref "IC6") (pin "3") (pinfunction "S_3") (pintype "passive"))
      (node (ref "Q1") (pin "1") (pinfunction "B_1") (pintype "passive"))
      (node (ref "R43") (pin "2") (pinfunction "2_2") (pintype "passive"))
    )
    (net (code "59") (name "Net-(R17-Pad1)") (class "Default")
      (node (ref "R17") (pin "1") (pinfunction "1_1") (pintype "passive"))
      (node (ref "R18") (pin "1") (pinfunction "1_1") (pintype "passive"))
      (node (ref "S1") (pin "3") (pinfunction "3_3") (pintype "passive"))
      (node (ref "S1") (pin "4") (pinfunction "4_4") (pintype "passive"))
    )
    (net (code "60") (name "unconnected-(IC1-3FG_PA7-Pad18)") (class "Default")
      (node (ref "IC1") (pin "18") (pinfunction "3FG_PA7_18") (pintype "bidirectional"))
    )
    (net (code "61") (name "unconnected-(IC1-OP1N-Pad22)") (class "Default")
      (node (ref "IC1") (pin "22") (pinfunction "OP1N_22") (pintype "input"))
    )
    (net (code "62") (name "unconnected-(IC1-OP1O-Pad21)") (class "Default")
      (node (ref "IC1") (pin "21") (pinfunction "OP1O_21") (pintype "output"))
    )
    (net (code "63") (name "unconnected-(IC1-OP1P-Pad23)") (class "Default")
      (node (ref "IC1") (pin "23") (pinfunction "OP1P_23") (pintype "input"))
    )
    (net (code "64") (name "unconnected-(J4-Pad2)") (class "Default")
      (node (ref "J4") (pin "2") (pinfunction "2_2") (pintype "passive+no_connect"))
    )
    (net (code "65") (name "unconnected-(J4-Pad6)") (class "Default")
      (node (ref "J4") (pin "6") (pinfunction "6_6") (pintype "passive+no_connect"))
    )
    (net (code "66") (name "unconnected-(J5-Pad6)") (class "Default")
      (node (ref "J5") (pin "6") (pinfunction "6_6") (pintype "passive+no_connect"))
    )
  )
)
